# ESP32-PICO-D4-MCU.net
KiCad netlist of a schematic drawn in Altium Designer
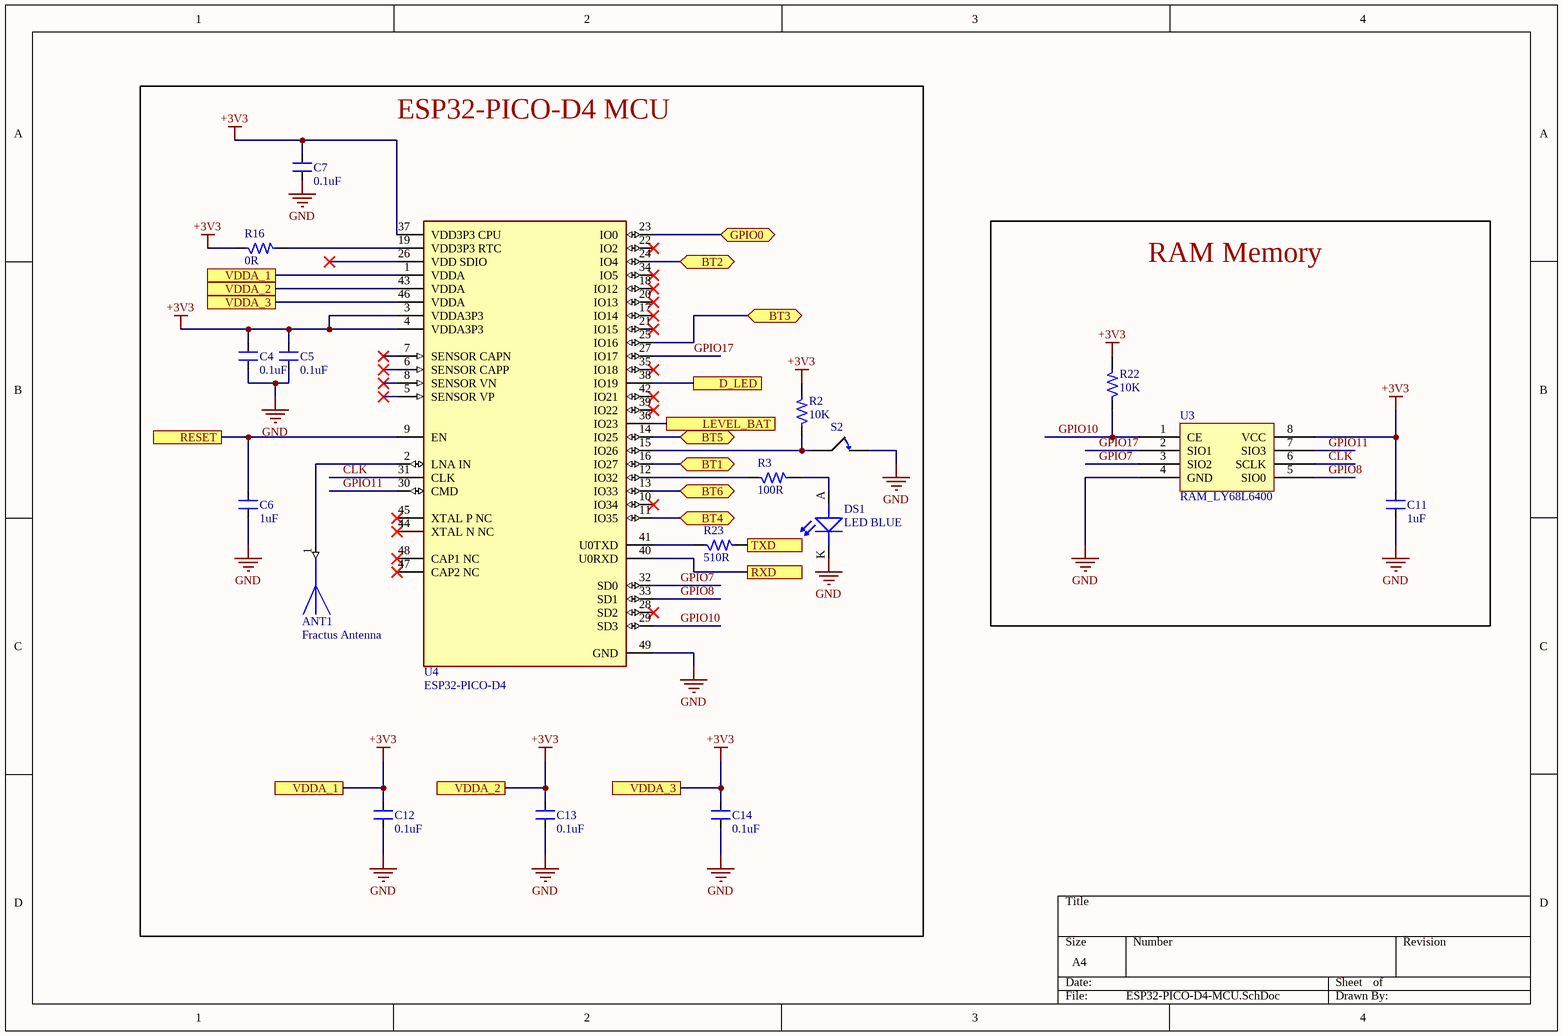
[diagram p0: ESP32-PICO-D4-MCU.SchDoc]

(export (version "E")
  (design (tool "Eeschema 10.0.6"))
  (components
    (comp (ref "ANT1")
      (value "Fractus Antenna")
      (footprint "Fractus_Antenna_NN01-102")
      (description "2.45GHz Bluetooth, WLAN, Zigbe Chip RF Antenna 2.4GHz ~ 2.5GHz 1.7dBi Solder Surface Mount")
      (libsource (lib "NOUMANPCBLIB") (part "ANT_2.45GHz_Bluetooth_WLAN_Zigbee_1.7dBi_NN01-102"))
    )
    (comp (ref "C4")
      (value "0.1uF")
      (footprint "CAP_0805")
      (description "0.1µF ±10% 50V Ceramic Capacitor X7R 0805 (2012 Metric)")
      (fields
        (field (name "MANUFACTURER") "Samsung")
        (field (name "MANUFACTURER PART NUMBER") "CL21B104KBCNNNC")
      )
      (libsource (lib "NOUMANPCBLIB") (part "CAP_0.1uF-50V-10%-0805"))
    )
    (comp (ref "C5")
      (value "0.1uF")
      (footprint "CAP_0805")
      (description "0.1µF ±10% 50V Ceramic Capacitor X7R 0805 (2012 Metric)")
      (fields
        (field (name "MANUFACTURER") "Samsung")
        (field (name "MANUFACTURER PART NUMBER") "CL21B104KBCNNNC")
      )
      (libsource (lib "NOUMANPCBLIB") (part "CAP_0.1uF-50V-10%-0805"))
    )
    (comp (ref "C6")
      (value "1uF")
      (footprint "CAP_0805")
      (description "1µF ±10% 50V Ceramic Capacitor X7R 0805 (2012 Metric)")
      (fields
        (field (name "MANUFACTURER") "Samsung")
        (field (name "MANUFACTURER PART NUMBER") "CL21B104KBCNNNC")
      )
      (libsource (lib "NOUMANPCBLIB") (part "CAP_1uF-50V-10%-0805_1"))
    )
    (comp (ref "C7")
      (value "0.1uF")
      (footprint "CAP_0805")
      (description "0.1µF ±10% 50V Ceramic Capacitor X7R 0805 (2012 Metric)")
      (fields
        (field (name "MANUFACTURER") "Samsung")
        (field (name "MANUFACTURER PART NUMBER") "CL21B104KBCNNNC")
      )
      (libsource (lib "NOUMANPCBLIB") (part "CAP_0.1uF-50V-10%-0805"))
    )
    (comp (ref "C11")
      (value "1uF")
      (footprint "CAP_0805")
      (description "1µF ±10% 50V Ceramic Capacitor X7R 0805 (2012 Metric)")
      (fields
        (field (name "MANUFACTURER") "Samsung")
        (field (name "MANUFACTURER PART NUMBER") "CL21B104KBCNNNC")
      )
      (libsource (lib "NOUMANPCBLIB") (part "CAP_1uF-50V-10%-0805_1"))
    )
    (comp (ref "C12")
      (value "0.1uF")
      (footprint "CAP_0805")
      (description "0.1µF ±10% 50V Ceramic Capacitor X7R 0805 (2012 Metric)")
      (fields
        (field (name "MANUFACTURER") "Samsung")
        (field (name "MANUFACTURER PART NUMBER") "CL21B104KBCNNNC")
      )
      (libsource (lib "NOUMANPCBLIB") (part "CAP_0.1uF-50V-10%-0805"))
    )
    (comp (ref "C13")
      (value "0.1uF")
      (footprint "CAP_0805")
      (description "0.1µF ±10% 50V Ceramic Capacitor X7R 0805 (2012 Metric)")
      (fields
        (field (name "MANUFACTURER") "Samsung")
        (field (name "MANUFACTURER PART NUMBER") "CL21B104KBCNNNC")
      )
      (libsource (lib "NOUMANPCBLIB") (part "CAP_0.1uF-50V-10%-0805"))
    )
    (comp (ref "C14")
      (value "0.1uF")
      (footprint "CAP_0805")
      (description "0.1µF ±10% 50V Ceramic Capacitor X7R 0805 (2012 Metric)")
      (fields
        (field (name "MANUFACTURER") "Samsung")
        (field (name "MANUFACTURER PART NUMBER") "CL21B104KBCNNNC")
      )
      (libsource (lib "NOUMANPCBLIB") (part "CAP_0.1uF-50V-10%-0805"))
    )
    (comp (ref "DS1")
      (value "LED BLUE")
      (footprint "LED_0805")
      (description "Blue 470nm LED Indication - Discrete 3.3V 0805 (2012 Metric)")
      (fields
        (field (name "MANUFACTURER") "Vishay Lite-On")
        (field (name "MANUFACTURER PART NUMBER") "LTST-C171TBKT")
      )
      (libsource (lib "NOUMANPCBLIB") (part "LED_BLUE-3V3-20mA-0805"))
    )
    (comp (ref "R2")
      (value "10K")
      (footprint "RES_0805")
      (description "10 kOhms ±1% 0.125W, 1/8W Chip Resistor 0805 (2012 Metric) Automotive AEC-Q200 Thick Film")
      (fields (field (name "MANUFACTURER") "CTS") (field (name "MANUFACTURER PART NUMBER") "WR08X1002FTL"))
      (libsource (lib "NOUMANPCBLIB") (part "RES_10K-0.125W-1%-0805"))
    )
    (comp (ref "R3")
      (value "100R")
      (footprint "RES_0805")
      (fields (field (name "MANUFACTURER") "Walsin") (field (name "MANUFACTURER PART NUMBER") "WR08X1000FTL"))
      (libsource (lib "NOUMANPCBLIB") (part "RES_100R-0.125W-1%-0805"))
    )
    (comp (ref "R16")
      (value "0R")
      (footprint "RES_0805")
      (description "0 Ohms Jumper 0.125W, 1/8W Chip Resistor 0805 (2012 Metric) Automotive AEC-Q200 Thick Film")
      (fields (field (name "MANUFACTURER") "Walsin") (field (name "MANUFACTURER PART NUMBER") "WR08X000PTL"))
      (libsource (lib "NOUMANPCBLIB") (part "RES_0R-0.125W-1%-0805"))
    )
    (comp (ref "R22")
      (value "10K")
      (footprint "RES_0805")
      (description "10 kOhms ±1% 0.125W, 1/8W Chip Resistor 0805 (2012 Metric) Automotive AEC-Q200 Thick Film")
      (fields (field (name "MANUFACTURER") "CTS") (field (name "MANUFACTURER PART NUMBER") "WR08X1002FTL"))
      (libsource (lib "NOUMANPCBLIB") (part "RES_10K-0.125W-1%-0805"))
    )
    (comp (ref "R23")
      (value "510R")
      (footprint "RES_0805")
      (description "510 Ohms ±1% 0.125W, 1/8W Chip Resistor 0805 (2012 Metric) Thin Film")
      (fields
        (field (name "MANUFACTURER") "Yageo")
        (field (name "MANUFACTURER PART NUMBER") "RT0805FRE07510RL")
      )
      (libsource (lib "NOUMANPCBLIB") (part "RES_510R-0.125W-1%-0805"))
    )
    (comp (ref "S2")
      (value "Button Tactile Switch, NO 0.05 A 0.8mm")
      (footprint "Button8014X17N")
      (fields
        (field (name "MANUFACTURER") "C & K")
        (field (name "MANUFACTURER PART NO.") "B3F1000")
        (field (name "CREATOR") "R Kanjee")
      )
      (libsource (lib "Omron Tactile Switches") (part "Button Tactile Switch, NO 0.05 A 0.8mm"))
    )
    (comp (ref "U3")
      (value "RAM_LY68L6400")
      (footprint "RAM_LY68L6400")
      (libsource (lib "IC_Espressif_Systems_ESP32-PICO-D4_eec") (part "RAM_LY68L6400"))
    )
    (comp (ref "U4")
      (value "ESP32-PICO-D4")
      (footprint "Espressif_Systems_0_IPC_A")
      (libsource (lib "IC_Espressif_Systems_ESP32-PICO-D4_eec") (part "ESP32-PICO-D4"))
    )
  )
  (nets
    (net (code "1") (name "+3V3") (class "Default")
      (node (ref "C11") (pin "2") (pinfunction "2_2") (pintype "passive"))
      (node (ref "C12") (pin "2") (pinfunction "2_2") (pintype "passive"))
      (node (ref "C13") (pin "2") (pinfunction "2_2") (pintype "passive"))
      (node (ref "C14") (pin "2") (pinfunction "2_2") (pintype "passive"))
      (node (ref "C4") (pin "2") (pinfunction "2_2") (pintype "passive"))
      (node (ref "C5") (pin "2") (pinfunction "2_2") (pintype "passive"))
      (node (ref "C7") (pin "2") (pinfunction "2_2") (pintype "passive"))
      (node (ref "R16") (pin "1") (pinfunction "1_1") (pintype "passive"))
      (node (ref "R2") (pin "2") (pinfunction "2_2") (pintype "passive"))
      (node (ref "R22") (pin "2") (pinfunction "2_2") (pintype "passive"))
      (node (ref "U3") (pin "8") (pinfunction "VCC_8") (pintype "passive"))
      (node (ref "U4") (pin "1") (pinfunction "VDDA_1") (pintype "power_in"))
      (node (ref "U4") (pin "3") (pinfunction "VDDA3P3_3") (pintype "power_in"))
      (node (ref "U4") (pin "37") (pinfunction "VDD3P3_CPU_37") (pintype "power_in"))
      (node (ref "U4") (pin "4") (pinfunction "VDDA3P3_4") (pintype "power_in"))
      (node (ref "U4") (pin "43") (pinfunction "VDDA_43") (pintype "power_in"))
      (node (ref "U4") (pin "46") (pinfunction "VDDA_46") (pintype "power_in"))
    )
    (net (code "2") (name "/BT1") (class "Default")
      (node (ref "U4") (pin "16") (pinfunction "IO27_16") (pintype "bidirectional"))
    )
    (net (code "3") (name "/BT2") (class "Default")
      (node (ref "U4") (pin "24") (pinfunction "IO4_24") (pintype "bidirectional"))
    )
    (net (code "4") (name "/BT3") (class "Default")
      (node (ref "U4") (pin "25") (pinfunction "IO16_25") (pintype "bidirectional"))
    )
    (net (code "5") (name "/BT4") (class "Default")
      (node (ref "U4") (pin "11") (pinfunction "IO35_11") (pintype "bidirectional"))
    )
    (net (code "6") (name "/BT5") (class "Default")
      (node (ref "U4") (pin "14") (pinfunction "IO25_14") (pintype "bidirectional"))
    )
    (net (code "7") (name "/BT6") (class "Default")
      (node (ref "U4") (pin "13") (pinfunction "IO33_13") (pintype "bidirectional"))
    )
    (net (code "8") (name "/CLK") (class "Default")
      (node (ref "U3") (pin "6") (pinfunction "SCLK_6") (pintype "passive"))
      (node (ref "U4") (pin "31") (pinfunction "CLK_31") (pintype "passive"))
    )
    (net (code "9") (name "/D_LED") (class "Default")
      (node (ref "U4") (pin "38") (pinfunction "IO19_38") (pintype "passive"))
    )
    (net (code "10") (name "/GPIO0") (class "Default")
      (node (ref "U4") (pin "23") (pinfunction "IO0_23") (pintype "bidirectional"))
    )
    (net (code "11") (name "/GPIO7") (class "Default")
      (node (ref "U3") (pin "3") (pinfunction "SIO2_3") (pintype "passive"))
      (node (ref "U4") (pin "32") (pinfunction "SD0_32") (pintype "bidirectional"))
    )
    (net (code "12") (name "/GPIO8") (class "Default")
      (node (ref "U3") (pin "5") (pinfunction "SIO0_5") (pintype "passive"))
      (node (ref "U4") (pin "33") (pinfunction "SD1_33") (pintype "bidirectional"))
    )
    (net (code "13") (name "/GPIO10") (class "Default")
      (node (ref "R22") (pin "1") (pinfunction "1_1") (pintype "passive"))
      (node (ref "U3") (pin "1") (pinfunction "CE_1") (pintype "passive"))
      (node (ref "U4") (pin "29") (pinfunction "SD3_29") (pintype "bidirectional"))
    )
    (net (code "14") (name "/GPIO11") (class "Default")
      (node (ref "U3") (pin "7") (pinfunction "SIO3_7") (pintype "passive"))
      (node (ref "U4") (pin "30") (pinfunction "CMD_30") (pintype "bidirectional"))
    )
    (net (code "15") (name "/GPIO17") (class "Default")
      (node (ref "U3") (pin "2") (pinfunction "SIO1_2") (pintype "passive"))
      (node (ref "U4") (pin "27") (pinfunction "IO17_27") (pintype "bidirectional"))
    )
    (net (code "16") (name "/LEVEL_BAT") (class "Default")
      (node (ref "U4") (pin "36") (pinfunction "IO23_36") (pintype "passive"))
    )
    (net (code "17") (name "/RESET") (class "Default")
      (node (ref "C6") (pin "2") (pinfunction "2_2") (pintype "passive"))
      (node (ref "U4") (pin "9") (pinfunction "EN_9") (pintype "passive"))
    )
    (net (code "18") (name "/RXD") (class "Default")
      (node (ref "U4") (pin "40") (pinfunction "U0RXD_40") (pintype "passive"))
    )
    (net (code "19") (name "/TXD") (class "Default")
      (node (ref "R23") (pin "2") (pinfunction "2_2") (pintype "passive"))
    )
    (net (code "20") (name "GND") (class "Default")
      (node (ref "C11") (pin "1") (pinfunction "1_1") (pintype "passive"))
      (node (ref "C12") (pin "1") (pinfunction "1_1") (pintype "passive"))
      (node (ref "C13") (pin "1") (pinfunction "1_1") (pintype "passive"))
      (node (ref "C14") (pin "1") (pinfunction "1_1") (pintype "passive"))
      (node (ref "C4") (pin "1") (pinfunction "1_1") (pintype "passive"))
      (node (ref "C5") (pin "1") (pinfunction "1_1") (pintype "passive"))
      (node (ref "C6") (pin "1") (pinfunction "1_1") (pintype "passive"))
      (node (ref "C7") (pin "1") (pinfunction "1_1") (pintype "passive"))
      (node (ref "DS1") (pin "K") (pinfunction "CATHODE_K") (pintype "passive"))
      (node (ref "S2") (pin "2") (pinfunction "2_2") (pintype "passive"))
      (node (ref "U3") (pin "4") (pinfunction "GND_4") (pintype "passive"))
      (node (ref "U4") (pin "49") (pinfunction "GND_49") (pintype "power_in"))
    )
    (net (code "21") (name "Net-(DS1-ANODE)") (class "Default")
      (node (ref "DS1") (pin "A") (pinfunction "ANODE_A") (pintype "passive"))
      (node (ref "R3") (pin "2") (pinfunction "2_2") (pintype "passive"))
    )
    (net (code "22") (name "Net-(U4-IO26)") (class "Default")
      (node (ref "R2") (pin "1") (pinfunction "1_1") (pintype "passive"))
      (node (ref "S2") (pin "1") (pinfunction "1_1") (pintype "passive"))
      (node (ref "U4") (pin "15") (pinfunction "IO26_15") (pintype "bidirectional"))
    )
    (net (code "23") (name "Net-(U4-IO32)") (class "Default")
      (node (ref "R3") (pin "1") (pinfunction "1_1") (pintype "passive"))
      (node (ref "U4") (pin "12") (pinfunction "IO32_12") (pintype "bidirectional"))
    )
    (net (code "24") (name "Net-(U4-LNA_IN)") (class "Default")
      (node (ref "ANT1") (pin "1") (pinfunction "1_1") (pintype "input"))
      (node (ref "U4") (pin "2") (pinfunction "LNA_IN_2") (pintype "bidirectional"))
    )
    (net (code "25") (name "Net-(U4-U0TXD)") (class "Default")
      (node (ref "R23") (pin "1") (pinfunction "1_1") (pintype "passive"))
      (node (ref "U4") (pin "41") (pinfunction "U0TXD_41") (pintype "passive"))
    )
    (net (code "26") (name "Net-(U4-VDD3P3_RTC)") (class "Default")
      (node (ref "R16") (pin "2") (pinfunction "2_2") (pintype "passive"))
      (node (ref "U4") (pin "19") (pinfunction "VDD3P3_RTC_19") (pintype "power_in"))
    )
    (net (code "27") (name "unconnected-(U4-CAP1_NC-Pad48)") (class "Default")
      (node (ref "U4") (pin "48") (pinfunction "CAP1_NC_48") (pintype "passive+no_connect"))
    )
    (net (code "28") (name "unconnected-(U4-CAP2_NC-Pad47)") (class "Default")
      (node (ref "U4") (pin "47") (pinfunction "CAP2_NC_47") (pintype "passive+no_connect"))
    )
    (net (code "29") (name "unconnected-(U4-IO2-Pad22)") (class "Default")
      (node (ref "U4") (pin "22") (pinfunction "IO2_22") (pintype "bidirectional+no_connect"))
    )
    (net (code "30") (name "unconnected-(U4-IO5-Pad34)") (class "Default")
      (node (ref "U4") (pin "34") (pinfunction "IO5_34") (pintype "bidirectional+no_connect"))
    )
    (net (code "31") (name "unconnected-(U4-IO12-Pad18)") (class "Default")
      (node (ref "U4") (pin "18") (pinfunction "IO12_18") (pintype "bidirectional+no_connect"))
    )
    (net (code "32") (name "unconnected-(U4-IO13-Pad20)") (class "Default")
      (node (ref "U4") (pin "20") (pinfunction "IO13_20") (pintype "bidirectional+no_connect"))
    )
    (net (code "33") (name "unconnected-(U4-IO14-Pad17)") (class "Default")
      (node (ref "U4") (pin "17") (pinfunction "IO14_17") (pintype "bidirectional+no_connect"))
    )
    (net (code "34") (name "unconnected-(U4-IO15-Pad21)") (class "Default")
      (node (ref "U4") (pin "21") (pinfunction "IO15_21") (pintype "bidirectional+no_connect"))
    )
    (net (code "35") (name "unconnected-(U4-IO18-Pad35)") (class "Default")
      (node (ref "U4") (pin "35") (pinfunction "IO18_35") (pintype "bidirectional+no_connect"))
    )
    (net (code "36") (name "unconnected-(U4-IO21-Pad42)") (class "Default")
      (node (ref "U4") (pin "42") (pinfunction "IO21_42") (pintype "bidirectional+no_connect"))
    )
    (net (code "37") (name "unconnected-(U4-IO22-Pad39)") (class "Default")
      (node (ref "U4") (pin "39") (pinfunction "IO22_39") (pintype "bidirectional+no_connect"))
    )
    (net (code "38") (name "unconnected-(U4-IO34-Pad10)") (class "Default")
      (node (ref "U4") (pin "10") (pinfunction "IO34_10") (pintype "bidirectional+no_connect"))
    )
    (net (code "39") (name "unconnected-(U4-SD2-Pad28)") (class "Default")
      (node (ref "U4") (pin "28") (pinfunction "SD2_28") (pintype "bidirectional+no_connect"))
    )
    (net (code "40") (name "unconnected-(U4-SENSOR_CAPN-Pad7)") (class "Default")
      (node (ref "U4") (pin "7") (pinfunction "SENSOR_CAPN_7") (pintype "input+no_connect"))
    )
    (net (code "41") (name "unconnected-(U4-SENSOR_CAPP-Pad6)") (class "Default")
      (node (ref "U4") (pin "6") (pinfunction "SENSOR_CAPP_6") (pintype "input+no_connect"))
    )
    (net (code "42") (name "unconnected-(U4-SENSOR_VN-Pad8)") (class "Default")
      (node (ref "U4") (pin "8") (pinfunction "SENSOR_VN_8") (pintype "input+no_connect"))
    )
    (net (code "43") (name "unconnected-(U4-SENSOR_VP-Pad5)") (class "Default")
      (node (ref "U4") (pin "5") (pinfunction "SENSOR_VP_5") (pintype "input+no_connect"))
    )
    (net (code "44") (name "unconnected-(U4-VDD_SDIO-Pad26)") (class "Default")
      (node (ref "U4") (pin "26") (pinfunction "VDD_SDIO_26") (pintype "power_in+no_connect"))
    )
    (net (code "45") (name "unconnected-(U4-XTAL_N_NC-Pad44)") (class "Default")
      (node (ref "U4") (pin "44") (pinfunction "XTAL_N_NC_44") (pintype "passive+no_connect"))
    )
    (net (code "46") (name "unconnected-(U4-XTAL_P_NC-Pad45)") (class "Default")
      (node (ref "U4") (pin "45") (pinfunction "XTAL_P_NC_45") (pintype "passive+no_connect"))
    )
  )
)
